# SchematicControlMotor.net
KiCad netlist of a schematic drawn in EAGLE
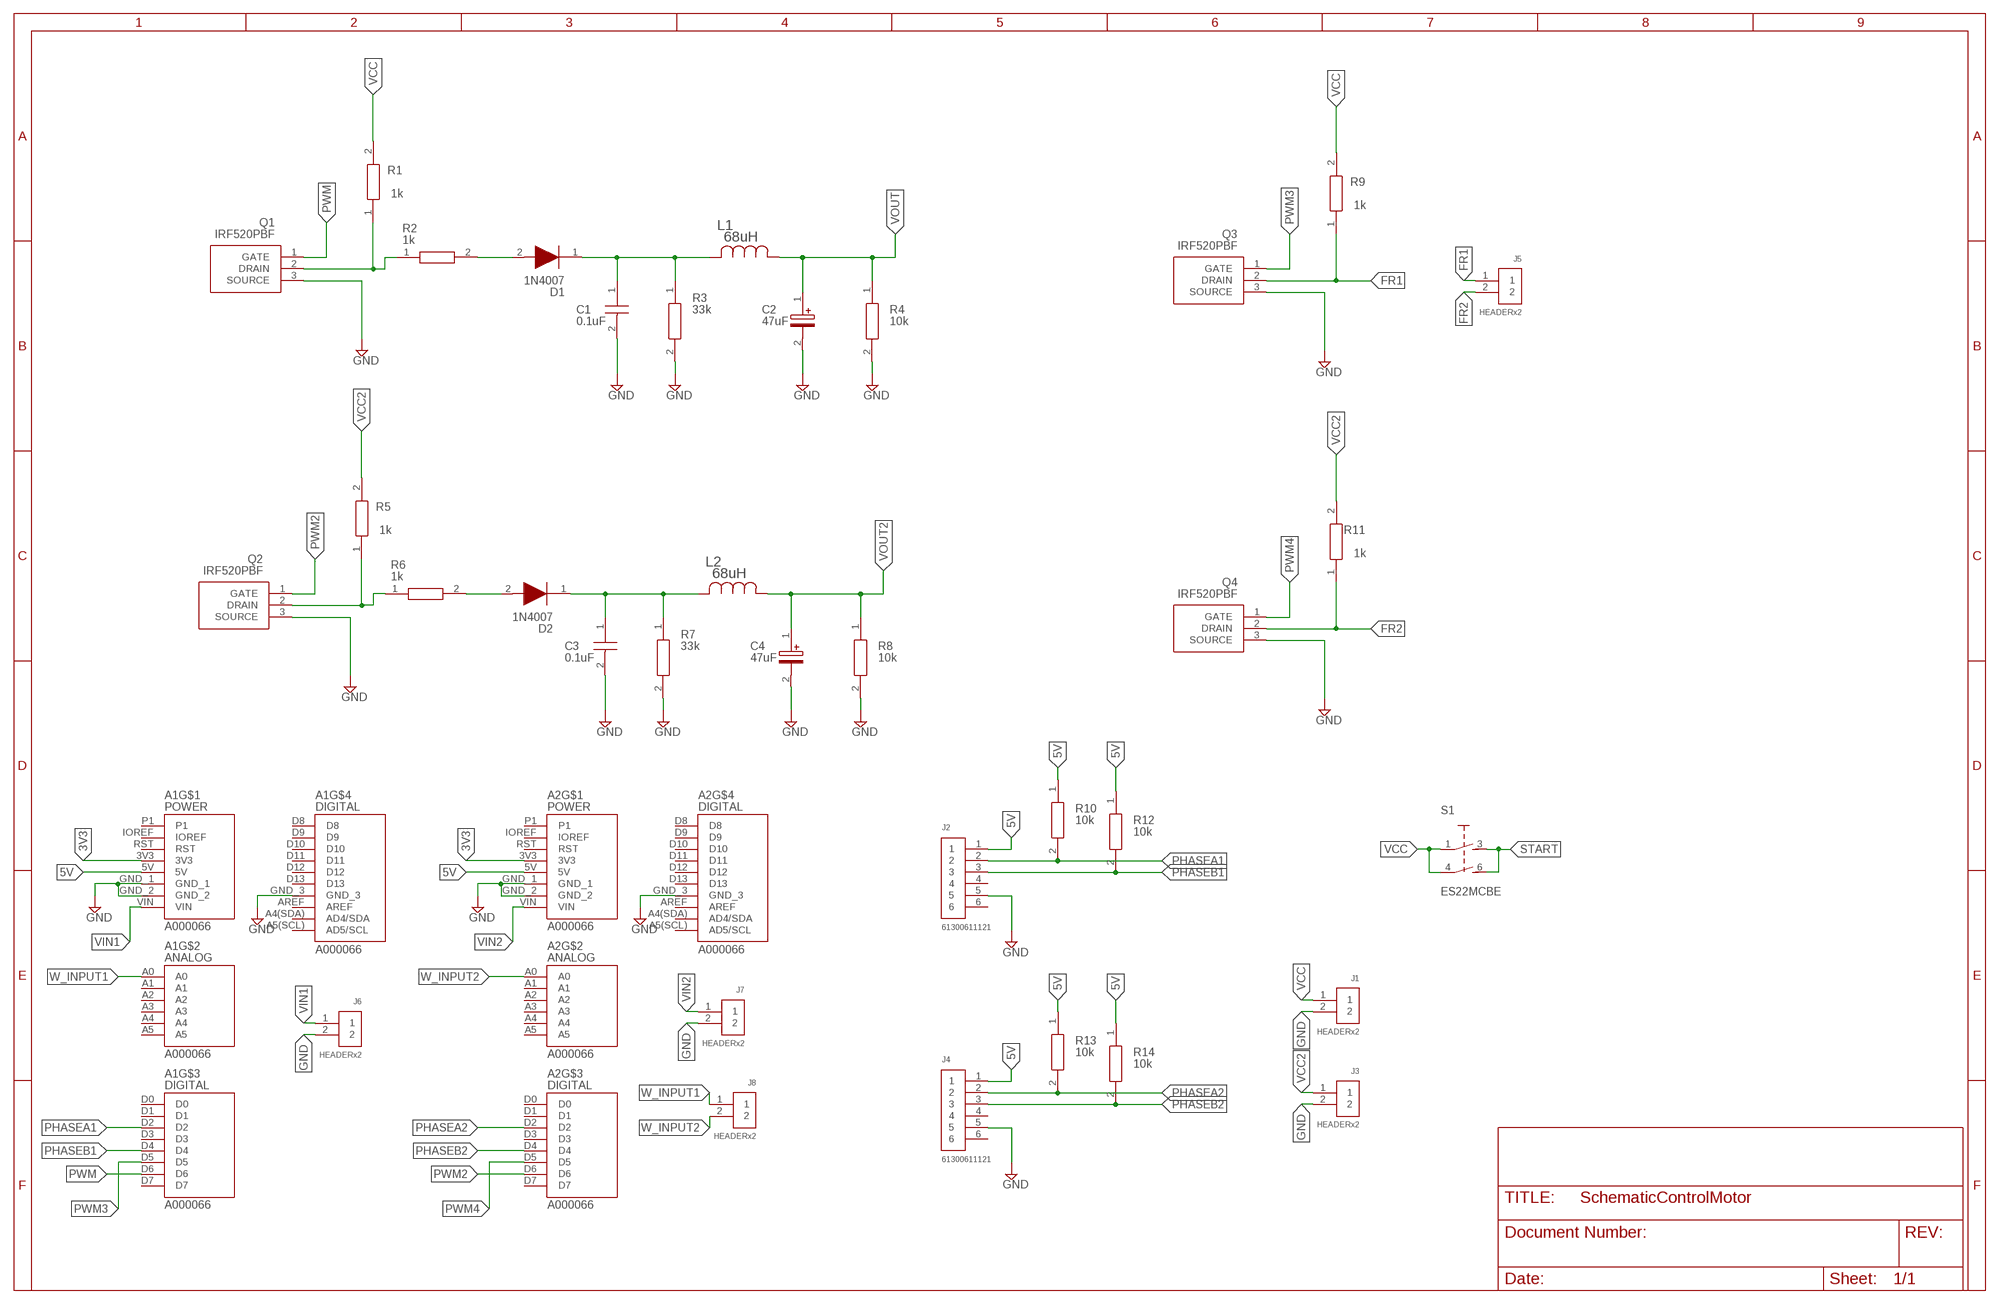
[diagram p0: schematic, sheet 1]

(export (version "E")
  (design (tool "Eeschema 10.0.6"))
  (components
    (comp (ref "A1")
      (value "A000066")
      (footprint "eagle-import:ARDUINO_A000066")
      (fields (field (name "MF") "Arduino") (field (name "MP") "ARDUINO UNO REV3"))
      (libsource (lib "eagle-import") (part "A000066"))
    )
    (comp (ref "A2")
      (value "A000066")
      (footprint "eagle-import:ARDUINO_A000066")
      (fields (field (name "MF") "Arduino") (field (name "MP") "ARDUINO UNO REV3"))
      (libsource (lib "eagle-import") (part "A000066"))
    )
    (comp (ref "C1")
      (value "0.1uF")
      (footprint "eagle-import:K104K10X7RF5TL2")
      (fields
        (field (name "MANUFACTURER_PART_NUMBER") "K104K10X7RF5TL2")
        (field (name "MOUSER_PART_NUMBER") "594-K104K10X7RF5TL2")
      )
      (libsource (lib "eagle-import") (part "CAPACITOR0.1U"))
    )
    (comp (ref "C2")
      (value "47uF")
      (footprint "eagle-import:CAPPRD200W50D525H1100")
      (fields
        (field (name "MANUFACTURER_PART_NUMBER") "SEK100M050ST")
        (field (name "MOUSER_PART_NUMBER") "539-SEK50V10")
      )
      (libsource (lib "eagle-import") (part "CAPACITOR10U"))
    )
    (comp (ref "C3")
      (value "0.1uF")
      (footprint "eagle-import:K104K10X7RF5TL2")
      (fields
        (field (name "MANUFACTURER_PART_NUMBER") "K104K10X7RF5TL2")
        (field (name "MOUSER_PART_NUMBER") "594-K104K10X7RF5TL2")
      )
      (libsource (lib "eagle-import") (part "CAPACITOR0.1U"))
    )
    (comp (ref "C4")
      (value "47uF")
      (footprint "eagle-import:CAPPRD200W50D525H1100")
      (fields
        (field (name "MANUFACTURER_PART_NUMBER") "SEK100M050ST")
        (field (name "MOUSER_PART_NUMBER") "539-SEK50V10")
      )
      (libsource (lib "eagle-import") (part "CAPACITOR10U"))
    )
    (comp (ref "D1")
      (value "1N4007")
      (footprint "eagle-import:DIOAD1405W58L465D235")
      (fields (field (name "MOUSER_PART_NUMBER") "637-1N4007"))
      (libsource (lib "eagle-import") (part "1N4007"))
    )
    (comp (ref "D2")
      (value "1N4007")
      (footprint "eagle-import:DIOAD1405W58L465D235")
      (fields (field (name "MOUSER_PART_NUMBER") "637-1N4007"))
      (libsource (lib "eagle-import") (part "1N4007"))
    )
    (comp (ref "J1")
      (value "HEADERx2")
      (footprint "eagle-import:61300211121")
      (fields
        (field (name "DIGI_KEY_PART_NUMBER") "732-5315-ND")
        (field (name "MANUFACTURER") "Wurth Electronics Inc.")
        (field (name "MPN") "61300211121")
        (field (name "CREATED_BY") "PCBLayout.com")
      )
      (libsource (lib "eagle-import") (part "61300211121"))
    )
    (comp (ref "J2")
      (value "61300611121")
      (footprint "eagle-import:61300611121")
      (fields
        (field (name "DIGI_KEY_PART_NUMBER") "732-5319-ND")
        (field (name "MANUFACTURER") "Wurth Electronics Inc.")
        (field (name "CREATED_BY") "PCBLayout.com")
      )
      (libsource (lib "eagle-import") (part "61300611121"))
    )
    (comp (ref "J3")
      (value "HEADERx2")
      (footprint "eagle-import:61300211121")
      (fields
        (field (name "DIGI_KEY_PART_NUMBER") "732-5315-ND")
        (field (name "MANUFACTURER") "Wurth Electronics Inc.")
        (field (name "MPN") "61300211121")
        (field (name "CREATED_BY") "PCBLayout.com")
      )
      (libsource (lib "eagle-import") (part "61300211121"))
    )
    (comp (ref "J4")
      (value "61300611121")
      (footprint "eagle-import:61300611121")
      (fields
        (field (name "DIGI_KEY_PART_NUMBER") "732-5319-ND")
        (field (name "MANUFACTURER") "Wurth Electronics Inc.")
        (field (name "CREATED_BY") "PCBLayout.com")
      )
      (libsource (lib "eagle-import") (part "61300611121"))
    )
    (comp (ref "J5")
      (value "HEADERx2")
      (footprint "eagle-import:61300211121")
      (fields
        (field (name "DIGI_KEY_PART_NUMBER") "732-5315-ND")
        (field (name "MANUFACTURER") "Wurth Electronics Inc.")
        (field (name "MPN") "61300211121")
        (field (name "CREATED_BY") "PCBLayout.com")
      )
      (libsource (lib "eagle-import") (part "61300211121"))
    )
    (comp (ref "J6")
      (value "HEADERx2")
      (footprint "eagle-import:61300211121")
      (fields
        (field (name "DIGI_KEY_PART_NUMBER") "732-5315-ND")
        (field (name "MANUFACTURER") "Wurth Electronics Inc.")
        (field (name "MPN") "61300211121")
        (field (name "CREATED_BY") "PCBLayout.com")
      )
      (libsource (lib "eagle-import") (part "61300211121"))
    )
    (comp (ref "J7")
      (value "HEADERx2")
      (footprint "eagle-import:61300211121")
      (fields
        (field (name "DIGI_KEY_PART_NUMBER") "732-5315-ND")
        (field (name "MANUFACTURER") "Wurth Electronics Inc.")
        (field (name "MPN") "61300211121")
        (field (name "CREATED_BY") "PCBLayout.com")
      )
      (libsource (lib "eagle-import") (part "61300211121"))
    )
    (comp (ref "J8")
      (value "HEADERx2")
      (footprint "eagle-import:61300211121")
      (fields
        (field (name "DIGI_KEY_PART_NUMBER") "732-5315-ND")
        (field (name "MANUFACTURER") "Wurth Electronics Inc.")
        (field (name "MPN") "61300211121")
        (field (name "CREATED_BY") "PCBLayout.com")
      )
      (libsource (lib "eagle-import") (part "61300211121"))
    )
    (comp (ref "L1")
      (value "68uH")
      (footprint "eagle-import:IND_BOURNS_78F")
      (fields
        (field (name "MANUFACTURER_PART_NUMBER") "78F680J-RC")
        (field (name "COPYRIGHT") "Copyright (C) 2023 Ultra Librarian. All rights reserved.")
      )
      (libsource (lib "eagle-import") (part "INDUCTOR68U"))
    )
    (comp (ref "L2")
      (value "68uH")
      (footprint "eagle-import:IND_BOURNS_78F")
      (fields
        (field (name "MANUFACTURER_PART_NUMBER") "78F680J-RC")
        (field (name "COPYRIGHT") "Copyright (C) 2023 Ultra Librarian. All rights reserved.")
      )
      (libsource (lib "eagle-import") (part "INDUCTOR68U"))
    )
    (comp (ref "Q1")
      (value "IRF520PBF")
      (footprint "eagle-import:TO254P465X1024X2050-3P")
      (fields (field (name "MOUSER_PART_NUMBER") "844-IRF520PBF"))
      (libsource (lib "eagle-import") (part "IRF520PBF"))
    )
    (comp (ref "Q2")
      (value "IRF520PBF")
      (footprint "eagle-import:TO254P465X1024X2050-3P")
      (fields (field (name "MOUSER_PART_NUMBER") "844-IRF520PBF"))
      (libsource (lib "eagle-import") (part "IRF520PBF"))
    )
    (comp (ref "Q3")
      (value "IRF520PBF")
      (footprint "eagle-import:TO254P465X1024X2050-3P")
      (fields (field (name "MOUSER_PART_NUMBER") "844-IRF520PBF"))
      (libsource (lib "eagle-import") (part "IRF520PBF"))
    )
    (comp (ref "Q4")
      (value "IRF520PBF")
      (footprint "eagle-import:TO254P465X1024X2050-3P")
      (fields (field (name "MOUSER_PART_NUMBER") "844-IRF520PBF"))
      (libsource (lib "eagle-import") (part "IRF520PBF"))
    )
    (comp (ref "R1")
      (value "1k")
      (footprint "eagle-import:RESAD1041W46L381D165")
      (fields
        (field (name "MANUFACTURER_PART_NUMBER") "CMF501K0000FHEB")
        (field (name "MOUSER_PART_NUMBER") "71-CMF501K0000FHEB")
      )
      (libsource (lib "eagle-import") (part "RESISTOR"))
    )
    (comp (ref "R2")
      (value "1k")
      (footprint "eagle-import:RESAD1041W46L381D165")
      (fields
        (field (name "MANUFACTURER_PART_NUMBER") "CMF501K0000FHEB")
        (field (name "MOUSER_PART_NUMBER") "71-CMF501K0000FHEB")
      )
      (libsource (lib "eagle-import") (part "RESISTOR"))
    )
    (comp (ref "R3")
      (value "33k")
      (footprint "eagle-import:RESAD1041W46L381D165")
      (fields
        (field (name "MANUFACTURER_PART_NUMBER") "CMF501K0000FHEB")
        (field (name "MOUSER_PART_NUMBER") "71-CMF501K0000FHEB")
      )
      (libsource (lib "eagle-import") (part "RESISTOR"))
    )
    (comp (ref "R4")
      (value "10k")
      (footprint "eagle-import:RESAD1041W46L381D165")
      (fields
        (field (name "MANUFACTURER_PART_NUMBER") "CMF501K0000FHEB")
        (field (name "MOUSER_PART_NUMBER") "71-CMF501K0000FHEB")
      )
      (libsource (lib "eagle-import") (part "RESISTOR"))
    )
    (comp (ref "R5")
      (value "1k")
      (footprint "eagle-import:RESAD1041W46L381D165")
      (fields
        (field (name "MANUFACTURER_PART_NUMBER") "CMF501K0000FHEB")
        (field (name "MOUSER_PART_NUMBER") "71-CMF501K0000FHEB")
      )
      (libsource (lib "eagle-import") (part "RESISTOR"))
    )
    (comp (ref "R6")
      (value "1k")
      (footprint "eagle-import:RESAD1041W46L381D165")
      (fields
        (field (name "MANUFACTURER_PART_NUMBER") "CMF501K0000FHEB")
        (field (name "MOUSER_PART_NUMBER") "71-CMF501K0000FHEB")
      )
      (libsource (lib "eagle-import") (part "RESISTOR"))
    )
    (comp (ref "R7")
      (value "33k")
      (footprint "eagle-import:RESAD1041W46L381D165")
      (fields
        (field (name "MANUFACTURER_PART_NUMBER") "CMF501K0000FHEB")
        (field (name "MOUSER_PART_NUMBER") "71-CMF501K0000FHEB")
      )
      (libsource (lib "eagle-import") (part "RESISTOR"))
    )
    (comp (ref "R8")
      (value "10k")
      (footprint "eagle-import:RESAD1041W46L381D165")
      (fields
        (field (name "MANUFACTURER_PART_NUMBER") "CMF501K0000FHEB")
        (field (name "MOUSER_PART_NUMBER") "71-CMF501K0000FHEB")
      )
      (libsource (lib "eagle-import") (part "RESISTOR"))
    )
    (comp (ref "R9")
      (value "1k")
      (footprint "eagle-import:RESAD1041W46L381D165")
      (fields
        (field (name "MANUFACTURER_PART_NUMBER") "CMF501K0000FHEB")
        (field (name "MOUSER_PART_NUMBER") "71-CMF501K0000FHEB")
      )
      (libsource (lib "eagle-import") (part "RESISTOR"))
    )
    (comp (ref "R10")
      (value "10k")
      (footprint "eagle-import:RESAD1041W46L381D165")
      (fields
        (field (name "MANUFACTURER_PART_NUMBER") "CMF501K0000FHEB")
        (field (name "MOUSER_PART_NUMBER") "71-CMF501K0000FHEB")
      )
      (libsource (lib "eagle-import") (part "RESISTOR"))
    )
    (comp (ref "R11")
      (value "1k")
      (footprint "eagle-import:RESAD1041W46L381D165")
      (fields
        (field (name "MANUFACTURER_PART_NUMBER") "CMF501K0000FHEB")
        (field (name "MOUSER_PART_NUMBER") "71-CMF501K0000FHEB")
      )
      (libsource (lib "eagle-import") (part "RESISTOR"))
    )
    (comp (ref "R12")
      (value "10k")
      (footprint "eagle-import:RESAD1041W46L381D165")
      (fields
        (field (name "MANUFACTURER_PART_NUMBER") "CMF501K0000FHEB")
        (field (name "MOUSER_PART_NUMBER") "71-CMF501K0000FHEB")
      )
      (libsource (lib "eagle-import") (part "RESISTOR"))
    )
    (comp (ref "R13")
      (value "10k")
      (footprint "eagle-import:RESAD1041W46L381D165")
      (fields
        (field (name "MANUFACTURER_PART_NUMBER") "CMF501K0000FHEB")
        (field (name "MOUSER_PART_NUMBER") "71-CMF501K0000FHEB")
      )
      (libsource (lib "eagle-import") (part "RESISTOR"))
    )
    (comp (ref "R14")
      (value "10k")
      (footprint "eagle-import:RESAD1041W46L381D165")
      (fields
        (field (name "MANUFACTURER_PART_NUMBER") "CMF501K0000FHEB")
        (field (name "MOUSER_PART_NUMBER") "71-CMF501K0000FHEB")
      )
      (libsource (lib "eagle-import") (part "RESISTOR"))
    )
    (comp (ref "S1")
      (value "ES22MCBE")
      (footprint "eagle-import:ES22MCBE")
      (fields
        (field (name "DIGIKEY_PARTNO") "CKN1815-ND")
        (field (name "MANUFACTURER") "C&K")
        (field (name "CREATED_BY") "PCBLayout.com")
      )
      (libsource (lib "eagle-import") (part "ES22MCBE"))
    )
  )
  (nets
    (net (code "1") (name "3V3") (class "Default")
      (node (ref "A1") (pin "3V3") (pinfunction "3V3_3V3") (pintype "power_in"))
      (node (ref "A2") (pin "3V3") (pinfunction "3V3_3V3") (pintype "power_in"))
    )
    (net (code "2") (name "5V") (class "Default")
      (node (ref "A1") (pin "5V") (pinfunction "5V_5V") (pintype "power_in"))
      (node (ref "A2") (pin "5V") (pinfunction "5V_5V") (pintype "power_in"))
      (node (ref "J2") (pin "1") (pinfunction "1_1") (pintype "passive"))
      (node (ref "J4") (pin "1") (pinfunction "1_1") (pintype "passive"))
      (node (ref "R10") (pin "1") (pinfunction "1_1") (pintype "bidirectional"))
      (node (ref "R12") (pin "1") (pinfunction "1_1") (pintype "bidirectional"))
      (node (ref "R13") (pin "1") (pinfunction "1_1") (pintype "bidirectional"))
      (node (ref "R14") (pin "1") (pinfunction "1_1") (pintype "bidirectional"))
    )
    (net (code "3") (name "FR1") (class "Default")
      (node (ref "J5") (pin "1") (pinfunction "1_1") (pintype "passive"))
      (node (ref "Q3") (pin "2") (pinfunction "DRAIN_2") (pintype "bidirectional"))
      (node (ref "R9") (pin "1") (pinfunction "1_1") (pintype "bidirectional"))
    )
    (net (code "4") (name "FR2") (class "Default")
      (node (ref "J5") (pin "2") (pinfunction "2_2") (pintype "passive"))
      (node (ref "Q4") (pin "2") (pinfunction "DRAIN_2") (pintype "bidirectional"))
      (node (ref "R11") (pin "1") (pinfunction "1_1") (pintype "bidirectional"))
    )
    (net (code "5") (name "GND") (class "Default")
      (node (ref "A1") (pin "GND_1") (pinfunction "GND_1_GND_1") (pintype "power_in"))
      (node (ref "A1") (pin "GND_2") (pinfunction "GND_2_GND_2") (pintype "power_in"))
      (node (ref "A1") (pin "GND_3") (pinfunction "GND_3_GND_3") (pintype "power_in"))
      (node (ref "A2") (pin "GND_1") (pinfunction "GND_1_GND_1") (pintype "power_in"))
      (node (ref "A2") (pin "GND_2") (pinfunction "GND_2_GND_2") (pintype "power_in"))
      (node (ref "A2") (pin "GND_3") (pinfunction "GND_3_GND_3") (pintype "power_in"))
      (node (ref "C1") (pin "2") (pinfunction "2_2") (pintype "bidirectional"))
      (node (ref "C2") (pin "2") (pinfunction "-_2") (pintype "bidirectional"))
      (node (ref "C3") (pin "2") (pinfunction "2_2") (pintype "bidirectional"))
      (node (ref "C4") (pin "2") (pinfunction "-_2") (pintype "bidirectional"))
      (node (ref "J1") (pin "2") (pinfunction "2_2") (pintype "passive"))
      (node (ref "J2") (pin "5") (pinfunction "5_5") (pintype "passive"))
      (node (ref "J3") (pin "2") (pinfunction "2_2") (pintype "passive"))
      (node (ref "J4") (pin "5") (pinfunction "5_5") (pintype "passive"))
      (node (ref "J6") (pin "2") (pinfunction "2_2") (pintype "passive"))
      (node (ref "J7") (pin "2") (pinfunction "2_2") (pintype "passive"))
      (node (ref "Q1") (pin "3") (pinfunction "SOURCE_3") (pintype "bidirectional"))
      (node (ref "Q2") (pin "3") (pinfunction "SOURCE_3") (pintype "bidirectional"))
      (node (ref "Q3") (pin "3") (pinfunction "SOURCE_3") (pintype "bidirectional"))
      (node (ref "Q4") (pin "3") (pinfunction "SOURCE_3") (pintype "bidirectional"))
      (node (ref "R3") (pin "2") (pinfunction "2_2") (pintype "bidirectional"))
      (node (ref "R4") (pin "2") (pinfunction "2_2") (pintype "bidirectional"))
      (node (ref "R7") (pin "2") (pinfunction "2_2") (pintype "bidirectional"))
      (node (ref "R8") (pin "2") (pinfunction "2_2") (pintype "bidirectional"))
    )
    (net (code "6") (name "Net-(D1-A)") (class "Default")
      (node (ref "D1") (pin "2") (pinfunction "A_2") (pintype "bidirectional"))
      (node (ref "R2") (pin "2") (pinfunction "2_2") (pintype "bidirectional"))
    )
    (net (code "7") (name "Net-(D1-K)") (class "Default")
      (node (ref "C1") (pin "1") (pinfunction "1_1") (pintype "bidirectional"))
      (node (ref "D1") (pin "1") (pinfunction "K_1") (pintype "bidirectional"))
      (node (ref "L1") (pin "2") (pinfunction "2_2") (pintype "passive"))
      (node (ref "R3") (pin "1") (pinfunction "1_1") (pintype "bidirectional"))
    )
    (net (code "8") (name "Net-(D2-A)") (class "Default")
      (node (ref "D2") (pin "2") (pinfunction "A_2") (pintype "bidirectional"))
      (node (ref "R6") (pin "2") (pinfunction "2_2") (pintype "bidirectional"))
    )
    (net (code "9") (name "Net-(D2-K)") (class "Default")
      (node (ref "C3") (pin "1") (pinfunction "1_1") (pintype "bidirectional"))
      (node (ref "D2") (pin "1") (pinfunction "K_1") (pintype "bidirectional"))
      (node (ref "L2") (pin "2") (pinfunction "2_2") (pintype "passive"))
      (node (ref "R7") (pin "1") (pinfunction "1_1") (pintype "bidirectional"))
    )
    (net (code "10") (name "Net-(Q1-DRAIN)") (class "Default")
      (node (ref "Q1") (pin "2") (pinfunction "DRAIN_2") (pintype "bidirectional"))
      (node (ref "R1") (pin "1") (pinfunction "1_1") (pintype "bidirectional"))
      (node (ref "R2") (pin "1") (pinfunction "1_1") (pintype "bidirectional"))
    )
    (net (code "11") (name "Net-(Q2-DRAIN)") (class "Default")
      (node (ref "Q2") (pin "2") (pinfunction "DRAIN_2") (pintype "bidirectional"))
      (node (ref "R5") (pin "1") (pinfunction "1_1") (pintype "bidirectional"))
      (node (ref "R6") (pin "1") (pinfunction "1_1") (pintype "bidirectional"))
    )
    (net (code "12") (name "PHASEA1") (class "Default")
      (node (ref "A1") (pin "D2") (pinfunction "D2_D2") (pintype "bidirectional"))
      (node (ref "J2") (pin "2") (pinfunction "2_2") (pintype "passive"))
      (node (ref "R10") (pin "2") (pinfunction "2_2") (pintype "bidirectional"))
    )
    (net (code "13") (name "PHASEA2") (class "Default")
      (node (ref "A2") (pin "D2") (pinfunction "D2_D2") (pintype "bidirectional"))
      (node (ref "J4") (pin "2") (pinfunction "2_2") (pintype "passive"))
      (node (ref "R13") (pin "2") (pinfunction "2_2") (pintype "bidirectional"))
    )
    (net (code "14") (name "PHASEB1") (class "Default")
      (node (ref "A1") (pin "D4") (pinfunction "D4_D4") (pintype "bidirectional"))
      (node (ref "J2") (pin "3") (pinfunction "3_3") (pintype "passive"))
      (node (ref "R12") (pin "2") (pinfunction "2_2") (pintype "bidirectional"))
    )
    (net (code "15") (name "PHASEB2") (class "Default")
      (node (ref "A2") (pin "D4") (pinfunction "D4_D4") (pintype "bidirectional"))
      (node (ref "J4") (pin "3") (pinfunction "3_3") (pintype "passive"))
      (node (ref "R14") (pin "2") (pinfunction "2_2") (pintype "bidirectional"))
    )
    (net (code "16") (name "PWM") (class "Default")
      (node (ref "A1") (pin "D6") (pinfunction "D6_D6") (pintype "bidirectional"))
      (node (ref "Q1") (pin "1") (pinfunction "GATE_1") (pintype "bidirectional"))
    )
    (net (code "17") (name "PWM2") (class "Default")
      (node (ref "A2") (pin "D6") (pinfunction "D6_D6") (pintype "bidirectional"))
      (node (ref "Q2") (pin "1") (pinfunction "GATE_1") (pintype "bidirectional"))
    )
    (net (code "18") (name "PWM3") (class "Default")
      (node (ref "A1") (pin "D5") (pinfunction "D5_D5") (pintype "bidirectional"))
      (node (ref "Q3") (pin "1") (pinfunction "GATE_1") (pintype "bidirectional"))
    )
    (net (code "19") (name "PWM4") (class "Default")
      (node (ref "A2") (pin "D5") (pinfunction "D5_D5") (pintype "bidirectional"))
      (node (ref "Q4") (pin "1") (pinfunction "GATE_1") (pintype "bidirectional"))
    )
    (net (code "20") (name "START") (class "Default")
      (node (ref "S1") (pin "3") (pinfunction "3_3") (pintype "passive"))
      (node (ref "S1") (pin "6") (pinfunction "6_6") (pintype "passive"))
    )
    (net (code "21") (name "VCC") (class "Default")
      (node (ref "J1") (pin "1") (pinfunction "1_1") (pintype "passive"))
      (node (ref "R1") (pin "2") (pinfunction "2_2") (pintype "bidirectional"))
      (node (ref "R9") (pin "2") (pinfunction "2_2") (pintype "bidirectional"))
      (node (ref "S1") (pin "1") (pinfunction "1_1") (pintype "passive"))
      (node (ref "S1") (pin "4") (pinfunction "4_4") (pintype "passive"))
    )
    (net (code "22") (name "VCC2") (class "Default")
      (node (ref "J3") (pin "1") (pinfunction "1_1") (pintype "passive"))
      (node (ref "R11") (pin "2") (pinfunction "2_2") (pintype "bidirectional"))
      (node (ref "R5") (pin "2") (pinfunction "2_2") (pintype "bidirectional"))
    )
    (net (code "23") (name "VIN1") (class "Default")
      (node (ref "A1") (pin "VIN") (pinfunction "VIN_VIN") (pintype "power_in"))
      (node (ref "J6") (pin "1") (pinfunction "1_1") (pintype "passive"))
    )
    (net (code "24") (name "VIN2") (class "Default")
      (node (ref "A2") (pin "VIN") (pinfunction "VIN_VIN") (pintype "power_in"))
      (node (ref "J7") (pin "1") (pinfunction "1_1") (pintype "passive"))
    )
    (net (code "25") (name "VOUT") (class "Default")
      (node (ref "C2") (pin "1") (pinfunction "+_1") (pintype "bidirectional"))
      (node (ref "L1") (pin "1") (pinfunction "1_1") (pintype "passive"))
      (node (ref "R4") (pin "1") (pinfunction "1_1") (pintype "bidirectional"))
    )
    (net (code "26") (name "VOUT2") (class "Default")
      (node (ref "C4") (pin "1") (pinfunction "+_1") (pintype "bidirectional"))
      (node (ref "L2") (pin "1") (pinfunction "1_1") (pintype "passive"))
      (node (ref "R8") (pin "1") (pinfunction "1_1") (pintype "bidirectional"))
    )
    (net (code "27") (name "W_INPUT1") (class "Default")
      (node (ref "A1") (pin "A0") (pinfunction "A0_A0") (pintype "bidirectional"))
      (node (ref "J8") (pin "1") (pinfunction "1_1") (pintype "passive"))
    )
    (net (code "28") (name "W_INPUT2") (class "Default")
      (node (ref "A2") (pin "A0") (pinfunction "A0_A0") (pintype "bidirectional"))
      (node (ref "J8") (pin "2") (pinfunction "2_2") (pintype "passive"))
    )
    (net (code "29") (name "unconnected-(A1-PadA1)") (class "Default")
      (node (ref "A1") (pin "A1") (pinfunction "A1_A1") (pintype "bidirectional"))
    )
    (net (code "30") (name "unconnected-(A1-PadA2)") (class "Default")
      (node (ref "A1") (pin "A2") (pinfunction "A2_A2") (pintype "bidirectional"))
    )
    (net (code "31") (name "unconnected-(A1-PadA3)") (class "Default")
      (node (ref "A1") (pin "A3") (pinfunction "A3_A3") (pintype "bidirectional"))
    )
    (net (code "32") (name "unconnected-(A1-PadA4)") (class "Default")
      (node (ref "A1") (pin "A4") (pinfunction "A4_A4") (pintype "bidirectional"))
    )
    (net (code "33") (name "unconnected-(A1-PadA5)") (class "Default")
      (node (ref "A1") (pin "A5") (pinfunction "A5_A5") (pintype "bidirectional"))
    )
    (net (code "34") (name "unconnected-(A1-PadAREF)") (class "Default")
      (node (ref "A1") (pin "AREF") (pinfunction "AREF_AREF") (pintype "bidirectional"))
    )
    (net (code "35") (name "unconnected-(A1-PadD0)") (class "Default")
      (node (ref "A1") (pin "D0") (pinfunction "D0_D0") (pintype "bidirectional"))
    )
    (net (code "36") (name "unconnected-(A1-PadD1)") (class "Default")
      (node (ref "A1") (pin "D1") (pinfunction "D1_D1") (pintype "bidirectional"))
    )
    (net (code "37") (name "unconnected-(A1-PadD3)") (class "Default")
      (node (ref "A1") (pin "D3") (pinfunction "D3_D3") (pintype "bidirectional"))
    )
    (net (code "38") (name "unconnected-(A1-PadD7)") (class "Default")
      (node (ref "A1") (pin "D7") (pinfunction "D7_D7") (pintype "bidirectional"))
    )
    (net (code "39") (name "unconnected-(A1-PadD8)") (class "Default")
      (node (ref "A1") (pin "D8") (pinfunction "D8_D8") (pintype "bidirectional"))
    )
    (net (code "40") (name "unconnected-(A1-PadD9)") (class "Default")
      (node (ref "A1") (pin "D9") (pinfunction "D9_D9") (pintype "bidirectional"))
    )
    (net (code "41") (name "unconnected-(A1-PadD10)") (class "Default")
      (node (ref "A1") (pin "D10") (pinfunction "D10_D10") (pintype "bidirectional"))
    )
    (net (code "42") (name "unconnected-(A1-PadD11)") (class "Default")
      (node (ref "A1") (pin "D11") (pinfunction "D11_D11") (pintype "bidirectional"))
    )
    (net (code "43") (name "unconnected-(A1-PadD12)") (class "Default")
      (node (ref "A1") (pin "D12") (pinfunction "D12_D12") (pintype "bidirectional"))
    )
    (net (code "44") (name "unconnected-(A1-PadD13)") (class "Default")
      (node (ref "A1") (pin "D13") (pinfunction "D13_D13") (pintype "bidirectional"))
    )
    (net (code "45") (name "unconnected-(A1-PadIOREF)") (class "Default")
      (node (ref "A1") (pin "IOREF") (pinfunction "IOREF_IOREF") (pintype "bidirectional"))
    )
    (net (code "46") (name "unconnected-(A1-PadP1)") (class "Default")
      (node (ref "A1") (pin "P1") (pinfunction "P1_P1") (pintype "bidirectional"))
    )
    (net (code "47") (name "unconnected-(A1-PadRST)") (class "Default")
      (node (ref "A1") (pin "RST") (pinfunction "RST_RST") (pintype "bidirectional"))
    )
    (net (code "48") (name "unconnected-(A1D-AD4{slash}SDA-PadA4(SDA))") (class "Default")
      (node (ref "A1") (pin "A4(SDA)") (pinfunction "AD4/SDA_A4(SDA)") (pintype "bidirectional"))
    )
    (net (code "49") (name "unconnected-(A1D-AD5{slash}SCL-PadA5(SCL))") (class "Default")
      (node (ref "A1") (pin "A5(SCL)") (pinfunction "AD5/SCL_A5(SCL)") (pintype "bidirectional"))
    )
    (net (code "50") (name "unconnected-(A2-PadA1)") (class "Default")
      (node (ref "A2") (pin "A1") (pinfunction "A1_A1") (pintype "bidirectional"))
    )
    (net (code "51") (name "unconnected-(A2-PadA2)") (class "Default")
      (node (ref "A2") (pin "A2") (pinfunction "A2_A2") (pintype "bidirectional"))
    )
    (net (code "52") (name "unconnected-(A2-PadA3)") (class "Default")
      (node (ref "A2") (pin "A3") (pinfunction "A3_A3") (pintype "bidirectional"))
    )
    (net (code "53") (name "unconnected-(A2-PadA4)") (class "Default")
      (node (ref "A2") (pin "A4") (pinfunction "A4_A4") (pintype "bidirectional"))
    )
    (net (code "54") (name "unconnected-(A2-PadA5)") (class "Default")
      (node (ref "A2") (pin "A5") (pinfunction "A5_A5") (pintype "bidirectional"))
    )
    (net (code "55") (name "unconnected-(A2-PadAREF)") (class "Default")
      (node (ref "A2") (pin "AREF") (pinfunction "AREF_AREF") (pintype "bidirectional"))
    )
    (net (code "56") (name "unconnected-(A2-PadD0)") (class "Default")
      (node (ref "A2") (pin "D0") (pinfunction "D0_D0") (pintype "bidirectional"))
    )
    (net (code "57") (name "unconnected-(A2-PadD1)") (class "Default")
      (node (ref "A2") (pin "D1") (pinfunction "D1_D1") (pintype "bidirectional"))
    )
    (net (code "58") (name "unconnected-(A2-PadD3)") (class "Default")
      (node (ref "A2") (pin "D3") (pinfunction "D3_D3") (pintype "bidirectional"))
    )
    (net (code "59") (name "unconnected-(A2-PadD7)") (class "Default")
      (node (ref "A2") (pin "D7") (pinfunction "D7_D7") (pintype "bidirectional"))
    )
    (net (code "60") (name "unconnected-(A2-PadD8)") (class "Default")
      (node (ref "A2") (pin "D8") (pinfunction "D8_D8") (pintype "bidirectional"))
    )
    (net (code "61") (name "unconnected-(A2-PadD9)") (class "Default")
      (node (ref "A2") (pin "D9") (pinfunction "D9_D9") (pintype "bidirectional"))
    )
    (net (code "62") (name "unconnected-(A2-PadD10)") (class "Default")
      (node (ref "A2") (pin "D10") (pinfunction "D10_D10") (pintype "bidirectional"))
    )
    (net (code "63") (name "unconnected-(A2-PadD11)") (class "Default")
      (node (ref "A2") (pin "D11") (pinfunction "D11_D11") (pintype "bidirectional"))
    )
    (net (code "64") (name "unconnected-(A2-PadD12)") (class "Default")
      (node (ref "A2") (pin "D12") (pinfunction "D12_D12") (pintype "bidirectional"))
    )
    (net (code "65") (name "unconnected-(A2-PadD13)") (class "Default")
      (node (ref "A2") (pin "D13") (pinfunction "D13_D13") (pintype "bidirectional"))
    )
    (net (code "66") (name "unconnected-(A2-PadIOREF)") (class "Default")
      (node (ref "A2") (pin "IOREF") (pinfunction "IOREF_IOREF") (pintype "bidirectional"))
    )
    (net (code "67") (name "unconnected-(A2-PadP1)") (class "Default")
      (node (ref "A2") (pin "P1") (pinfunction "P1_P1") (pintype "bidirectional"))
    )
    (net (code "68") (name "unconnected-(A2-PadRST)") (class "Default")
      (node (ref "A2") (pin "RST") (pinfunction "RST_RST") (pintype "bidirectional"))
    )
    (net (code "69") (name "unconnected-(A2D-AD4{slash}SDA-PadA4(SDA))") (class "Default")
      (node (ref "A2") (pin "A4(SDA)") (pinfunction "AD4/SDA_A4(SDA)") (pintype "bidirectional"))
    )
    (net (code "70") (name "unconnected-(A2D-AD5{slash}SCL-PadA5(SCL))") (class "Default")
      (node (ref "A2") (pin "A5(SCL)") (pinfunction "AD5/SCL_A5(SCL)") (pintype "bidirectional"))
    )
    (net (code "71") (name "unconnected-(J2-Pad4)") (class "Default")
      (node (ref "J2") (pin "4") (pinfunction "4_4") (pintype "passive"))
    )
    (net (code "72") (name "unconnected-(J2-Pad6)") (class "Default")
      (node (ref "J2") (pin "6") (pinfunction "6_6") (pintype "passive"))
    )
    (net (code "73") (name "unconnected-(J4-Pad4)") (class "Default")
      (node (ref "J4") (pin "4") (pinfunction "4_4") (pintype "passive"))
    )
    (net (code "74") (name "unconnected-(J4-Pad6)") (class "Default")
      (node (ref "J4") (pin "6") (pinfunction "6_6") (pintype "passive"))
    )
  )
)
